# F28335_FanOut.net
KiCad netlist of a schematic drawn in Altium Designer
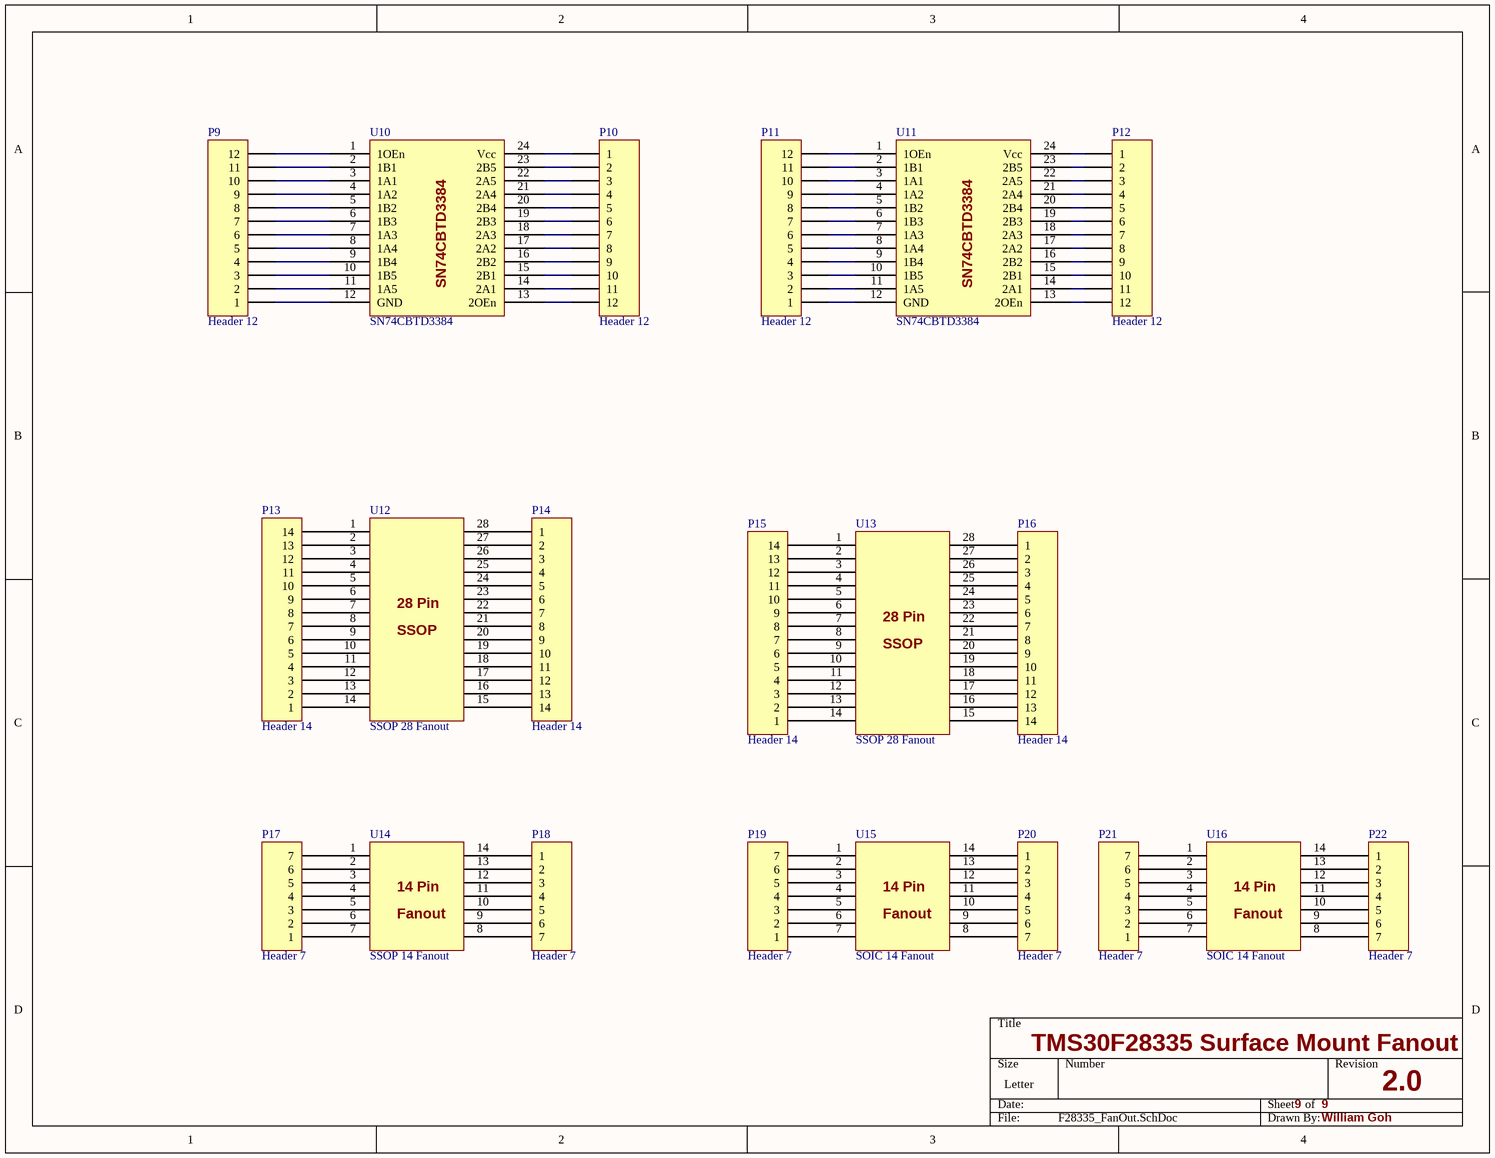
[diagram p0: F28335_FanOut.SchDoc]

(export (version "E")
  (design (tool "Eeschema 10.0.6"))
  (components
    (comp (ref "P9")
      (value "Header 12")
      (footprint "HDR1X12")
      (description "Header, 12-Pin")
      (fields (field (name "PUBLISHER") "Altium Limited"))
      (libsource (lib "Miscellaneous Connectors") (part "Header 12"))
    )
    (comp (ref "P10")
      (value "Header 12")
      (footprint "HDR1X12")
      (description "Header, 12-Pin")
      (fields (field (name "PUBLISHER") "Altium Limited"))
      (libsource (lib "") (part "Header 12_1"))
    )
    (comp (ref "P11")
      (value "Header 12")
      (footprint "HDR1X12")
      (description "Header, 12-Pin")
      (fields (field (name "PUBLISHER") "Altium Limited"))
      (libsource (lib "Miscellaneous Connectors") (part "Header 12"))
    )
    (comp (ref "P12")
      (value "Header 12")
      (footprint "HDR1X12")
      (description "Header, 12-Pin")
      (fields (field (name "PUBLISHER") "Altium Limited"))
      (libsource (lib "") (part "Header 12_1"))
    )
    (comp (ref "P13")
      (value "Header 14")
      (footprint "HDR1X14")
      (description "Header, 14-Pin")
      (fields (field (name "PUBLISHER") "Altium Limited"))
      (libsource (lib "") (part "Header 14_1"))
    )
    (comp (ref "P14")
      (value "Header 14")
      (footprint "HDR1X14")
      (description "Header, 14-Pin")
      (fields (field (name "PUBLISHER") "Altium Limited"))
      (libsource (lib "Miscellaneous Connectors") (part "Header 14"))
    )
    (comp (ref "P15")
      (value "Header 14")
      (footprint "HDR1X14")
      (description "Header, 14-Pin")
      (fields (field (name "PUBLISHER") "Altium Limited"))
      (libsource (lib "") (part "Header 14_1"))
    )
    (comp (ref "P16")
      (value "Header 14")
      (footprint "HDR1X14")
      (description "Header, 14-Pin")
      (fields (field (name "PUBLISHER") "Altium Limited"))
      (libsource (lib "Miscellaneous Connectors") (part "Header 14"))
    )
    (comp (ref "P17")
      (value "Header 7")
      (footprint "HDR1X7")
      (description "Header, 7-Pin")
      (fields (field (name "PUBLISHER") "Altium Limited"))
      (libsource (lib "") (part "Header 7_1"))
    )
    (comp (ref "P18")
      (value "Header 7")
      (footprint "HDR1X7")
      (description "Header, 7-Pin")
      (fields (field (name "PUBLISHER") "Altium Limited"))
      (libsource (lib "Miscellaneous Connectors") (part "Header 7"))
    )
    (comp (ref "P19")
      (value "Header 7")
      (footprint "HDR1X7")
      (description "Header, 7-Pin")
      (fields (field (name "PUBLISHER") "Altium Limited"))
      (libsource (lib "") (part "Header 7_1"))
    )
    (comp (ref "P20")
      (value "Header 7")
      (footprint "HDR1X7")
      (description "Header, 7-Pin")
      (fields (field (name "PUBLISHER") "Altium Limited"))
      (libsource (lib "Miscellaneous Connectors") (part "Header 7"))
    )
    (comp (ref "P21")
      (value "Header 7")
      (footprint "HDR1X7")
      (description "Header, 7-Pin")
      (fields (field (name "PUBLISHER") "Altium Limited"))
      (libsource (lib "") (part "Header 7_1"))
    )
    (comp (ref "P22")
      (value "Header 7")
      (footprint "HDR1X7")
      (description "Header, 7-Pin")
      (fields (field (name "PUBLISHER") "Altium Limited"))
      (libsource (lib "Miscellaneous Connectors") (part "Header 7"))
    )
    (comp (ref "U10")
      (value "SN74CBTD3384")
      (footprint "DW-24")
      (description "10-Bit FET Bus Switches With Level Shifting")
      (libsource (lib "F28335_DSC_Breakout") (part "SN74CBTD3384"))
    )
    (comp (ref "U11")
      (value "SN74CBTD3384")
      (footprint "DW-24")
      (description "10-Bit FET Bus Switches With Level Shifting")
      (libsource (lib "F28335_DSC_Breakout") (part "SN74CBTD3384"))
    )
    (comp (ref "U12")
      (value "SSOP 28 Fanout")
      (footprint "SSOP-28 Fan out")
      (libsource (lib "F28335_DSC_Breakout") (part "SSOP 28 Fanout"))
    )
    (comp (ref "U13")
      (value "SSOP 28 Fanout")
      (footprint "SSOP-28 Fan out")
      (libsource (lib "F28335_DSC_Breakout") (part "SSOP 28 Fanout"))
    )
    (comp (ref "U14")
      (value "SSOP 14 Fanout")
      (footprint "SSOP-14 Fan out")
      (libsource (lib "F28335_DSC_Breakout") (part "SSOP 14 Fanout"))
    )
    (comp (ref "U15")
      (value "SOIC 14 Fanout")
      (footprint "SOIC-14 Fan out")
      (libsource (lib "F28335_DSC_Breakout") (part "SSOP 14 Fanout"))
    )
    (comp (ref "U16")
      (value "SOIC 14 Fanout")
      (footprint "SOIC-14 Fan out")
      (libsource (lib "F28335_DSC_Breakout") (part "SSOP 14 Fanout"))
    )
  )
  (nets
    (net (code "1") (name "Net-(P13-Pad1)") (class "Default")
      (node (ref "P13") (pin "1") (pinfunction "1_1") (pintype "passive"))
      (node (ref "U12") (pin "14") (pintype "passive"))
    )
    (net (code "2") (name "Net-(P13-Pad2)") (class "Default")
      (node (ref "P13") (pin "2") (pinfunction "2_2") (pintype "passive"))
      (node (ref "U12") (pin "13") (pintype "passive"))
    )
    (net (code "3") (name "Net-(P13-Pad3)") (class "Default")
      (node (ref "P13") (pin "3") (pinfunction "3_3") (pintype "passive"))
      (node (ref "U12") (pin "12") (pintype "passive"))
    )
    (net (code "4") (name "Net-(P13-Pad4)") (class "Default")
      (node (ref "P13") (pin "4") (pinfunction "4_4") (pintype "passive"))
      (node (ref "U12") (pin "11") (pintype "passive"))
    )
    (net (code "5") (name "Net-(P13-Pad5)") (class "Default")
      (node (ref "P13") (pin "5") (pinfunction "5_5") (pintype "passive"))
      (node (ref "U12") (pin "10") (pintype "passive"))
    )
    (net (code "6") (name "Net-(P13-Pad6)") (class "Default")
      (node (ref "P13") (pin "6") (pinfunction "6_6") (pintype "passive"))
      (node (ref "U12") (pin "9") (pintype "passive"))
    )
    (net (code "7") (name "Net-(P13-Pad7)") (class "Default")
      (node (ref "P13") (pin "7") (pinfunction "7_7") (pintype "passive"))
      (node (ref "U12") (pin "8") (pintype "passive"))
    )
    (net (code "8") (name "Net-(P13-Pad8)") (class "Default")
      (node (ref "P13") (pin "8") (pinfunction "8_8") (pintype "passive"))
      (node (ref "U12") (pin "7") (pintype "passive"))
    )
    (net (code "9") (name "Net-(P13-Pad9)") (class "Default")
      (node (ref "P13") (pin "9") (pinfunction "9_9") (pintype "passive"))
      (node (ref "U12") (pin "6") (pintype "passive"))
    )
    (net (code "10") (name "Net-(P13-Pad10)") (class "Default")
      (node (ref "P13") (pin "10") (pinfunction "10_10") (pintype "passive"))
      (node (ref "U12") (pin "5") (pintype "passive"))
    )
    (net (code "11") (name "Net-(P13-Pad11)") (class "Default")
      (node (ref "P13") (pin "11") (pinfunction "11_11") (pintype "passive"))
      (node (ref "U12") (pin "4") (pintype "passive"))
    )
    (net (code "12") (name "Net-(P13-Pad12)") (class "Default")
      (node (ref "P13") (pin "12") (pinfunction "12_12") (pintype "passive"))
      (node (ref "U12") (pin "3") (pintype "passive"))
    )
    (net (code "13") (name "Net-(P13-Pad13)") (class "Default")
      (node (ref "P13") (pin "13") (pinfunction "13_13") (pintype "passive"))
      (node (ref "U12") (pin "2") (pintype "passive"))
    )
    (net (code "14") (name "Net-(P13-Pad14)") (class "Default")
      (node (ref "P13") (pin "14") (pinfunction "14_14") (pintype "passive"))
      (node (ref "U12") (pin "1") (pintype "passive"))
    )
    (net (code "15") (name "Net-(P14-Pad1)") (class "Default")
      (node (ref "P14") (pin "1") (pinfunction "1_1") (pintype "passive"))
      (node (ref "U12") (pin "28") (pintype "passive"))
    )
    (net (code "16") (name "Net-(P14-Pad2)") (class "Default")
      (node (ref "P14") (pin "2") (pinfunction "2_2") (pintype "passive"))
      (node (ref "U12") (pin "27") (pintype "passive"))
    )
    (net (code "17") (name "Net-(P14-Pad3)") (class "Default")
      (node (ref "P14") (pin "3") (pinfunction "3_3") (pintype "passive"))
      (node (ref "U12") (pin "26") (pintype "passive"))
    )
    (net (code "18") (name "Net-(P14-Pad4)") (class "Default")
      (node (ref "P14") (pin "4") (pinfunction "4_4") (pintype "passive"))
      (node (ref "U12") (pin "25") (pintype "passive"))
    )
    (net (code "19") (name "Net-(P14-Pad5)") (class "Default")
      (node (ref "P14") (pin "5") (pinfunction "5_5") (pintype "passive"))
      (node (ref "U12") (pin "24") (pintype "passive"))
    )
    (net (code "20") (name "Net-(P14-Pad6)") (class "Default")
      (node (ref "P14") (pin "6") (pinfunction "6_6") (pintype "passive"))
      (node (ref "U12") (pin "23") (pintype "passive"))
    )
    (net (code "21") (name "Net-(P14-Pad7)") (class "Default")
      (node (ref "P14") (pin "7") (pinfunction "7_7") (pintype "passive"))
      (node (ref "U12") (pin "22") (pintype "passive"))
    )
    (net (code "22") (name "Net-(P14-Pad8)") (class "Default")
      (node (ref "P14") (pin "8") (pinfunction "8_8") (pintype "passive"))
      (node (ref "U12") (pin "21") (pintype "passive"))
    )
    (net (code "23") (name "Net-(P14-Pad9)") (class "Default")
      (node (ref "P14") (pin "9") (pinfunction "9_9") (pintype "passive"))
      (node (ref "U12") (pin "20") (pintype "passive"))
    )
    (net (code "24") (name "Net-(P14-Pad10)") (class "Default")
      (node (ref "P14") (pin "10") (pinfunction "10_10") (pintype "passive"))
      (node (ref "U12") (pin "19") (pintype "passive"))
    )
    (net (code "25") (name "Net-(P14-Pad11)") (class "Default")
      (node (ref "P14") (pin "11") (pinfunction "11_11") (pintype "passive"))
      (node (ref "U12") (pin "18") (pintype "passive"))
    )
    (net (code "26") (name "Net-(P14-Pad12)") (class "Default")
      (node (ref "P14") (pin "12") (pinfunction "12_12") (pintype "passive"))
      (node (ref "U12") (pin "17") (pintype "passive"))
    )
    (net (code "27") (name "Net-(P14-Pad13)") (class "Default")
      (node (ref "P14") (pin "13") (pinfunction "13_13") (pintype "passive"))
      (node (ref "U12") (pin "16") (pintype "passive"))
    )
    (net (code "28") (name "Net-(P14-Pad14)") (class "Default")
      (node (ref "P14") (pin "14") (pinfunction "14_14") (pintype "passive"))
      (node (ref "U12") (pin "15") (pintype "passive"))
    )
    (net (code "29") (name "Net-(P15-Pad1)") (class "Default")
      (node (ref "P15") (pin "1") (pinfunction "1_1") (pintype "passive"))
      (node (ref "U13") (pin "14") (pintype "passive"))
    )
    (net (code "30") (name "Net-(P15-Pad2)") (class "Default")
      (node (ref "P15") (pin "2") (pinfunction "2_2") (pintype "passive"))
      (node (ref "U13") (pin "13") (pintype "passive"))
    )
    (net (code "31") (name "Net-(P15-Pad3)") (class "Default")
      (node (ref "P15") (pin "3") (pinfunction "3_3") (pintype "passive"))
      (node (ref "U13") (pin "12") (pintype "passive"))
    )
    (net (code "32") (name "Net-(P15-Pad4)") (class "Default")
      (node (ref "P15") (pin "4") (pinfunction "4_4") (pintype "passive"))
      (node (ref "U13") (pin "11") (pintype "passive"))
    )
    (net (code "33") (name "Net-(P15-Pad5)") (class "Default")
      (node (ref "P15") (pin "5") (pinfunction "5_5") (pintype "passive"))
      (node (ref "U13") (pin "10") (pintype "passive"))
    )
    (net (code "34") (name "Net-(P15-Pad6)") (class "Default")
      (node (ref "P15") (pin "6") (pinfunction "6_6") (pintype "passive"))
      (node (ref "U13") (pin "9") (pintype "passive"))
    )
    (net (code "35") (name "Net-(P15-Pad7)") (class "Default")
      (node (ref "P15") (pin "7") (pinfunction "7_7") (pintype "passive"))
      (node (ref "U13") (pin "8") (pintype "passive"))
    )
    (net (code "36") (name "Net-(P15-Pad8)") (class "Default")
      (node (ref "P15") (pin "8") (pinfunction "8_8") (pintype "passive"))
      (node (ref "U13") (pin "7") (pintype "passive"))
    )
    (net (code "37") (name "Net-(P15-Pad9)") (class "Default")
      (node (ref "P15") (pin "9") (pinfunction "9_9") (pintype "passive"))
      (node (ref "U13") (pin "6") (pintype "passive"))
    )
    (net (code "38") (name "Net-(P15-Pad10)") (class "Default")
      (node (ref "P15") (pin "10") (pinfunction "10_10") (pintype "passive"))
      (node (ref "U13") (pin "5") (pintype "passive"))
    )
    (net (code "39") (name "Net-(P15-Pad11)") (class "Default")
      (node (ref "P15") (pin "11") (pinfunction "11_11") (pintype "passive"))
      (node (ref "U13") (pin "4") (pintype "passive"))
    )
    (net (code "40") (name "Net-(P15-Pad12)") (class "Default")
      (node (ref "P15") (pin "12") (pinfunction "12_12") (pintype "passive"))
      (node (ref "U13") (pin "3") (pintype "passive"))
    )
    (net (code "41") (name "Net-(P15-Pad13)") (class "Default")
      (node (ref "P15") (pin "13") (pinfunction "13_13") (pintype "passive"))
      (node (ref "U13") (pin "2") (pintype "passive"))
    )
    (net (code "42") (name "Net-(P15-Pad14)") (class "Default")
      (node (ref "P15") (pin "14") (pinfunction "14_14") (pintype "passive"))
      (node (ref "U13") (pin "1") (pintype "passive"))
    )
    (net (code "43") (name "Net-(P16-Pad1)") (class "Default")
      (node (ref "P16") (pin "1") (pinfunction "1_1") (pintype "passive"))
      (node (ref "U13") (pin "28") (pintype "passive"))
    )
    (net (code "44") (name "Net-(P16-Pad2)") (class "Default")
      (node (ref "P16") (pin "2") (pinfunction "2_2") (pintype "passive"))
      (node (ref "U13") (pin "27") (pintype "passive"))
    )
    (net (code "45") (name "Net-(P16-Pad3)") (class "Default")
      (node (ref "P16") (pin "3") (pinfunction "3_3") (pintype "passive"))
      (node (ref "U13") (pin "26") (pintype "passive"))
    )
    (net (code "46") (name "Net-(P16-Pad4)") (class "Default")
      (node (ref "P16") (pin "4") (pinfunction "4_4") (pintype "passive"))
      (node (ref "U13") (pin "25") (pintype "passive"))
    )
    (net (code "47") (name "Net-(P16-Pad5)") (class "Default")
      (node (ref "P16") (pin "5") (pinfunction "5_5") (pintype "passive"))
      (node (ref "U13") (pin "24") (pintype "passive"))
    )
    (net (code "48") (name "Net-(P16-Pad6)") (class "Default")
      (node (ref "P16") (pin "6") (pinfunction "6_6") (pintype "passive"))
      (node (ref "U13") (pin "23") (pintype "passive"))
    )
    (net (code "49") (name "Net-(P16-Pad7)") (class "Default")
      (node (ref "P16") (pin "7") (pinfunction "7_7") (pintype "passive"))
      (node (ref "U13") (pin "22") (pintype "passive"))
    )
    (net (code "50") (name "Net-(P16-Pad8)") (class "Default")
      (node (ref "P16") (pin "8") (pinfunction "8_8") (pintype "passive"))
      (node (ref "U13") (pin "21") (pintype "passive"))
    )
    (net (code "51") (name "Net-(P16-Pad9)") (class "Default")
      (node (ref "P16") (pin "9") (pinfunction "9_9") (pintype "passive"))
      (node (ref "U13") (pin "20") (pintype "passive"))
    )
    (net (code "52") (name "Net-(P16-Pad10)") (class "Default")
      (node (ref "P16") (pin "10") (pinfunction "10_10") (pintype "passive"))
      (node (ref "U13") (pin "19") (pintype "passive"))
    )
    (net (code "53") (name "Net-(P16-Pad11)") (class "Default")
      (node (ref "P16") (pin "11") (pinfunction "11_11") (pintype "passive"))
      (node (ref "U13") (pin "18") (pintype "passive"))
    )
    (net (code "54") (name "Net-(P16-Pad12)") (class "Default")
      (node (ref "P16") (pin "12") (pinfunction "12_12") (pintype "passive"))
      (node (ref "U13") (pin "17") (pintype "passive"))
    )
    (net (code "55") (name "Net-(P16-Pad13)") (class "Default")
      (node (ref "P16") (pin "13") (pinfunction "13_13") (pintype "passive"))
      (node (ref "U13") (pin "16") (pintype "passive"))
    )
    (net (code "56") (name "Net-(P16-Pad14)") (class "Default")
      (node (ref "P16") (pin "14") (pinfunction "14_14") (pintype "passive"))
      (node (ref "U13") (pin "15") (pintype "passive"))
    )
    (net (code "57") (name "Net-(P17-Pad1)") (class "Default")
      (node (ref "P17") (pin "1") (pinfunction "1_1") (pintype "passive"))
      (node (ref "U14") (pin "7") (pintype "passive"))
    )
    (net (code "58") (name "Net-(P17-Pad2)") (class "Default")
      (node (ref "P17") (pin "2") (pinfunction "2_2") (pintype "passive"))
      (node (ref "U14") (pin "6") (pintype "passive"))
    )
    (net (code "59") (name "Net-(P17-Pad3)") (class "Default")
      (node (ref "P17") (pin "3") (pinfunction "3_3") (pintype "passive"))
      (node (ref "U14") (pin "5") (pintype "passive"))
    )
    (net (code "60") (name "Net-(P17-Pad4)") (class "Default")
      (node (ref "P17") (pin "4") (pinfunction "4_4") (pintype "passive"))
      (node (ref "U14") (pin "4") (pintype "passive"))
    )
    (net (code "61") (name "Net-(P17-Pad5)") (class "Default")
      (node (ref "P17") (pin "5") (pinfunction "5_5") (pintype "passive"))
      (node (ref "U14") (pin "3") (pintype "passive"))
    )
    (net (code "62") (name "Net-(P17-Pad6)") (class "Default")
      (node (ref "P17") (pin "6") (pinfunction "6_6") (pintype "passive"))
      (node (ref "U14") (pin "2") (pintype "passive"))
    )
    (net (code "63") (name "Net-(P17-Pad7)") (class "Default")
      (node (ref "P17") (pin "7") (pinfunction "7_7") (pintype "passive"))
      (node (ref "U14") (pin "1") (pintype "passive"))
    )
    (net (code "64") (name "Net-(P18-Pad1)") (class "Default")
      (node (ref "P18") (pin "1") (pinfunction "1_1") (pintype "passive"))
      (node (ref "U14") (pin "14") (pintype "passive"))
    )
    (net (code "65") (name "Net-(P18-Pad2)") (class "Default")
      (node (ref "P18") (pin "2") (pinfunction "2_2") (pintype "passive"))
      (node (ref "U14") (pin "13") (pintype "passive"))
    )
    (net (code "66") (name "Net-(P18-Pad3)") (class "Default")
      (node (ref "P18") (pin "3") (pinfunction "3_3") (pintype "passive"))
      (node (ref "U14") (pin "12") (pintype "passive"))
    )
    (net (code "67") (name "Net-(P18-Pad4)") (class "Default")
      (node (ref "P18") (pin "4") (pinfunction "4_4") (pintype "passive"))
      (node (ref "U14") (pin "11") (pintype "passive"))
    )
    (net (code "68") (name "Net-(P18-Pad5)") (class "Default")
      (node (ref "P18") (pin "5") (pinfunction "5_5") (pintype "passive"))
      (node (ref "U14") (pin "10") (pintype "passive"))
    )
    (net (code "69") (name "Net-(P18-Pad6)") (class "Default")
      (node (ref "P18") (pin "6") (pinfunction "6_6") (pintype "passive"))
      (node (ref "U14") (pin "9") (pintype "passive"))
    )
    (net (code "70") (name "Net-(P18-Pad7)") (class "Default")
      (node (ref "P18") (pin "7") (pinfunction "7_7") (pintype "passive"))
      (node (ref "U14") (pin "8") (pintype "passive"))
    )
    (net (code "71") (name "Net-(P19-Pad1)") (class "Default")
      (node (ref "P19") (pin "1") (pinfunction "1_1") (pintype "passive"))
      (node (ref "U15") (pin "7") (pintype "passive"))
    )
    (net (code "72") (name "Net-(P19-Pad2)") (class "Default")
      (node (ref "P19") (pin "2") (pinfunction "2_2") (pintype "passive"))
      (node (ref "U15") (pin "6") (pintype "passive"))
    )
    (net (code "73") (name "Net-(P19-Pad3)") (class "Default")
      (node (ref "P19") (pin "3") (pinfunction "3_3") (pintype "passive"))
      (node (ref "U15") (pin "5") (pintype "passive"))
    )
    (net (code "74") (name "Net-(P19-Pad4)") (class "Default")
      (node (ref "P19") (pin "4") (pinfunction "4_4") (pintype "passive"))
      (node (ref "U15") (pin "4") (pintype "passive"))
    )
    (net (code "75") (name "Net-(P19-Pad5)") (class "Default")
      (node (ref "P19") (pin "5") (pinfunction "5_5") (pintype "passive"))
      (node (ref "U15") (pin "3") (pintype "passive"))
    )
    (net (code "76") (name "Net-(P19-Pad6)") (class "Default")
      (node (ref "P19") (pin "6") (pinfunction "6_6") (pintype "passive"))
      (node (ref "U15") (pin "2") (pintype "passive"))
    )
    (net (code "77") (name "Net-(P19-Pad7)") (class "Default")
      (node (ref "P19") (pin "7") (pinfunction "7_7") (pintype "passive"))
      (node (ref "U15") (pin "1") (pintype "passive"))
    )
    (net (code "78") (name "Net-(P20-Pad1)") (class "Default")
      (node (ref "P20") (pin "1") (pinfunction "1_1") (pintype "passive"))
      (node (ref "U15") (pin "14") (pintype "passive"))
    )
    (net (code "79") (name "Net-(P20-Pad2)") (class "Default")
      (node (ref "P20") (pin "2") (pinfunction "2_2") (pintype "passive"))
      (node (ref "U15") (pin "13") (pintype "passive"))
    )
    (net (code "80") (name "Net-(P20-Pad3)") (class "Default")
      (node (ref "P20") (pin "3") (pinfunction "3_3") (pintype "passive"))
      (node (ref "U15") (pin "12") (pintype "passive"))
    )
    (net (code "81") (name "Net-(P20-Pad4)") (class "Default")
      (node (ref "P20") (pin "4") (pinfunction "4_4") (pintype "passive"))
      (node (ref "U15") (pin "11") (pintype "passive"))
    )
    (net (code "82") (name "Net-(P20-Pad5)") (class "Default")
      (node (ref "P20") (pin "5") (pinfunction "5_5") (pintype "passive"))
      (node (ref "U15") (pin "10") (pintype "passive"))
    )
    (net (code "83") (name "Net-(P20-Pad6)") (class "Default")
      (node (ref "P20") (pin "6") (pinfunction "6_6") (pintype "passive"))
      (node (ref "U15") (pin "9") (pintype "passive"))
    )
    (net (code "84") (name "Net-(P20-Pad7)") (class "Default")
      (node (ref "P20") (pin "7") (pinfunction "7_7") (pintype "passive"))
      (node (ref "U15") (pin "8") (pintype "passive"))
    )
    (net (code "85") (name "Net-(P21-Pad1)") (class "Default")
      (node (ref "P21") (pin "1") (pinfunction "1_1") (pintype "passive"))
      (node (ref "U16") (pin "7") (pintype "passive"))
    )
    (net (code "86") (name "Net-(P21-Pad2)") (class "Default")
      (node (ref "P21") (pin "2") (pinfunction "2_2") (pintype "passive"))
      (node (ref "U16") (pin "6") (pintype "passive"))
    )
    (net (code "87") (name "Net-(P21-Pad3)") (class "Default")
      (node (ref "P21") (pin "3") (pinfunction "3_3") (pintype "passive"))
      (node (ref "U16") (pin "5") (pintype "passive"))
    )
    (net (code "88") (name "Net-(P21-Pad4)") (class "Default")
      (node (ref "P21") (pin "4") (pinfunction "4_4") (pintype "passive"))
      (node (ref "U16") (pin "4") (pintype "passive"))
    )
    (net (code "89") (name "Net-(P21-Pad5)") (class "Default")
      (node (ref "P21") (pin "5") (pinfunction "5_5") (pintype "passive"))
      (node (ref "U16") (pin "3") (pintype "passive"))
    )
    (net (code "90") (name "Net-(P21-Pad6)") (class "Default")
      (node (ref "P21") (pin "6") (pinfunction "6_6") (pintype "passive"))
      (node (ref "U16") (pin "2") (pintype "passive"))
    )
    (net (code "91") (name "Net-(P21-Pad7)") (class "Default")
      (node (ref "P21") (pin "7") (pinfunction "7_7") (pintype "passive"))
      (node (ref "U16") (pin "1") (pintype "passive"))
    )
    (net (code "92") (name "Net-(P22-Pad1)") (class "Default")
      (node (ref "P22") (pin "1") (pinfunction "1_1") (pintype "passive"))
      (node (ref "U16") (pin "14") (pintype "passive"))
    )
    (net (code "93") (name "Net-(P22-Pad2)") (class "Default")
      (node (ref "P22") (pin "2") (pinfunction "2_2") (pintype "passive"))
      (node (ref "U16") (pin "13") (pintype "passive"))
    )
    (net (code "94") (name "Net-(P22-Pad3)") (class "Default")
      (node (ref "P22") (pin "3") (pinfunction "3_3") (pintype "passive"))
      (node (ref "U16") (pin "12") (pintype "passive"))
    )
    (net (code "95") (name "Net-(P22-Pad4)") (class "Default")
      (node (ref "P22") (pin "4") (pinfunction "4_4") (pintype "passive"))
      (node (ref "U16") (pin "11") (pintype "passive"))
    )
    (net (code "96") (name "Net-(P22-Pad5)") (class "Default")
      (node (ref "P22") (pin "5") (pinfunction "5_5") (pintype "passive"))
      (node (ref "U16") (pin "10") (pintype "passive"))
    )
    (net (code "97") (name "Net-(P22-Pad6)") (class "Default")
      (node (ref "P22") (pin "6") (pinfunction "6_6") (pintype "passive"))
      (node (ref "U16") (pin "9") (pintype "passive"))
    )
    (net (code "98") (name "Net-(P22-Pad7)") (class "Default")
      (node (ref "P22") (pin "7") (pinfunction "7_7") (pintype "passive"))
      (node (ref "U16") (pin "8") (pintype "passive"))
    )
    (net (code "99") (name "Net-(U10-1A1)") (class "Default")
      (node (ref "P9") (pin "10") (pinfunction "10_10") (pintype "passive"))
      (node (ref "U10") (pin "3") (pinfunction "1A1_3") (pintype "passive"))
    )
    (net (code "100") (name "Net-(U10-1A2)") (class "Default")
      (node (ref "P9") (pin "9") (pinfunction "9_9") (pintype "passive"))
      (node (ref "U10") (pin "4") (pinfunction "1A2_4") (pintype "passive"))
    )
    (net (code "101") (name "Net-(U10-1A3)") (class "Default")
      (node (ref "P9") (pin "6") (pinfunction "6_6") (pintype "passive"))
      (node (ref "U10") (pin "7") (pinfunction "1A3_7") (pintype "passive"))
    )
    (net (code "102") (name "Net-(U10-1A4)") (class "Default")
      (node (ref "P9") (pin "5") (pinfunction "5_5") (pintype "passive"))
      (node (ref "U10") (pin "8") (pinfunction "1A4_8") (pintype "passive"))
    )
    (net (code "103") (name "Net-(U10-1A5)") (class "Default")
      (node (ref "P9") (pin "2") (pinfunction "2_2") (pintype "passive"))
      (node (ref "U10") (pin "11") (pinfunction "1A5_11") (pintype "passive"))
    )
    (net (code "104") (name "Net-(U10-1B1)") (class "Default")
      (node (ref "P9") (pin "11") (pinfunction "11_11") (pintype "passive"))
      (node (ref "U10") (pin "2") (pinfunction "1B1_2") (pintype "passive"))
    )
    (net (code "105") (name "Net-(U10-1B2)") (class "Default")
      (node (ref "P9") (pin "8") (pinfunction "8_8") (pintype "passive"))
      (node (ref "U10") (pin "5") (pinfunction "1B2_5") (pintype "passive"))
    )
    (net (code "106") (name "Net-(U10-1B3)") (class "Default")
      (node (ref "P9") (pin "7") (pinfunction "7_7") (pintype "passive"))
      (node (ref "U10") (pin "6") (pinfunction "1B3_6") (pintype "passive"))
    )
    (net (code "107") (name "Net-(U10-1B4)") (class "Default")
      (node (ref "P9") (pin "4") (pinfunction "4_4") (pintype "passive"))
      (node (ref "U10") (pin "9") (pinfunction "1B4_9") (pintype "passive"))
    )
    (net (code "108") (name "Net-(U10-1B5)") (class "Default")
      (node (ref "P9") (pin "3") (pinfunction "3_3") (pintype "passive"))
      (node (ref "U10") (pin "10") (pinfunction "1B5_10") (pintype "passive"))
    )
    (net (code "109") (name "Net-(U10-1OEn)") (class "Default")
      (node (ref "P9") (pin "12") (pinfunction "12_12") (pintype "passive"))
      (node (ref "U10") (pin "1") (pinfunction "1OEn_1") (pintype "passive"))
    )
    (net (code "110") (name "Net-(U10-2A1)") (class "Default")
      (node (ref "P10") (pin "11") (pinfunction "11_11") (pintype "passive"))
      (node (ref "U10") (pin "14") (pinfunction "2A1_14") (pintype "passive"))
    )
    (net (code "111") (name "Net-(U10-2A2)") (class "Default")
      (node (ref "P10") (pin "8") (pinfunction "8_8") (pintype "passive"))
      (node (ref "U10") (pin "17") (pinfunction "2A2_17") (pintype "passive"))
    )
    (net (code "112") (name "Net-(U10-2A3)") (class "Default")
      (node (ref "P10") (pin "7") (pinfunction "7_7") (pintype "passive"))
      (node (ref "U10") (pin "18") (pinfunction "2A3_18") (pintype "passive"))
    )
    (net (code "113") (name "Net-(U10-2A4)") (class "Default")
      (node (ref "P10") (pin "4") (pinfunction "4_4") (pintype "passive"))
      (node (ref "U10") (pin "21") (pinfunction "2A4_21") (pintype "passive"))
    )
    (net (code "114") (name "Net-(U10-2A5)") (class "Default")
      (node (ref "P10") (pin "3") (pinfunction "3_3") (pintype "passive"))
      (node (ref "U10") (pin "22") (pinfunction "2A5_22") (pintype "passive"))
    )
    (net (code "115") (name "Net-(U10-2B1)") (class "Default")
      (node (ref "P10") (pin "10") (pinfunction "10_10") (pintype "passive"))
      (node (ref "U10") (pin "15") (pinfunction "2B1_15") (pintype "passive"))
    )
    (net (code "116") (name "Net-(U10-2B2)") (class "Default")
      (node (ref "P10") (pin "9") (pinfunction "9_9") (pintype "passive"))
      (node (ref "U10") (pin "16") (pinfunction "2B2_16") (pintype "passive"))
    )
    (net (code "117") (name "Net-(U10-2B3)") (class "Default")
      (node (ref "P10") (pin "6") (pinfunction "6_6") (pintype "passive"))
      (node (ref "U10") (pin "19") (pinfunction "2B3_19") (pintype "passive"))
    )
    (net (code "118") (name "Net-(U10-2B4)") (class "Default")
      (node (ref "P10") (pin "5") (pinfunction "5_5") (pintype "passive"))
      (node (ref "U10") (pin "20") (pinfunction "2B4_20") (pintype "passive"))
    )
    (net (code "119") (name "Net-(U10-2B5)") (class "Default")
      (node (ref "P10") (pin "2") (pinfunction "2_2") (pintype "passive"))
      (node (ref "U10") (pin "23") (pinfunction "2B5_23") (pintype "passive"))
    )
    (net (code "120") (name "Net-(U10-2OEn)") (class "Default")
      (node (ref "P10") (pin "12") (pinfunction "12_12") (pintype "passive"))
      (node (ref "U10") (pin "13") (pinfunction "2OEn_13") (pintype "passive"))
    )
    (net (code "121") (name "Net-(U10-GND)") (class "Default")
      (node (ref "P9") (pin "1") (pinfunction "1_1") (pintype "passive"))
      (node (ref "U10") (pin "12") (pinfunction "GND_12") (pintype "passive"))
    )
    (net (code "122") (name "Net-(U10-Vcc)") (class "Default")
      (node (ref "P10") (pin "1") (pinfunction "1_1") (pintype "passive"))
      (node (ref "U10") (pin "24") (pinfunction "Vcc_24") (pintype "passive"))
    )
    (net (code "123") (name "Net-(U11-1A1)") (class "Default")
      (node (ref "P11") (pin "10") (pinfunction "10_10") (pintype "passive"))
      (node (ref "U11") (pin "3") (pinfunction "1A1_3") (pintype "passive"))
    )
    (net (code "124") (name "Net-(U11-1A2)") (class "Default")
      (node (ref "P11") (pin "9") (pinfunction "9_9") (pintype "passive"))
      (node (ref "U11") (pin "4") (pinfunction "1A2_4") (pintype "passive"))
    )
    (net (code "125") (name "Net-(U11-1A3)") (class "Default")
      (node (ref "P11") (pin "6") (pinfunction "6_6") (pintype "passive"))
      (node (ref "U11") (pin "7") (pinfunction "1A3_7") (pintype "passive"))
    )
    (net (code "126") (name "Net-(U11-1A4)") (class "Default")
      (node (ref "P11") (pin "5") (pinfunction "5_5") (pintype "passive"))
      (node (ref "U11") (pin "8") (pinfunction "1A4_8") (pintype "passive"))
    )
    (net (code "127") (name "Net-(U11-1A5)") (class "Default")
      (node (ref "P11") (pin "2") (pinfunction "2_2") (pintype "passive"))
      (node (ref "U11") (pin "11") (pinfunction "1A5_11") (pintype "passive"))
    )
    (net (code "128") (name "Net-(U11-1B1)") (class "Default")
      (node (ref "P11") (pin "11") (pinfunction "11_11") (pintype "passive"))
      (node (ref "U11") (pin "2") (pinfunction "1B1_2") (pintype "passive"))
    )
    (net (code "129") (name "Net-(U11-1B2)") (class "Default")
      (node (ref "P11") (pin "8") (pinfunction "8_8") (pintype "passive"))
      (node (ref "U11") (pin "5") (pinfunction "1B2_5") (pintype "passive"))
    )
    (net (code "130") (name "Net-(U11-1B3)") (class "Default")
      (node (ref "P11") (pin "7") (pinfunction "7_7") (pintype "passive"))
      (node (ref "U11") (pin "6") (pinfunction "1B3_6") (pintype "passive"))
    )
    (net (code "131") (name "Net-(U11-1B4)") (class "Default")
      (node (ref "P11") (pin "4") (pinfunction "4_4") (pintype "passive"))
      (node (ref "U11") (pin "9") (pinfunction "1B4_9") (pintype "passive"))
    )
    (net (code "132") (name "Net-(U11-1B5)") (class "Default")
      (node (ref "P11") (pin "3") (pinfunction "3_3") (pintype "passive"))
      (node (ref "U11") (pin "10") (pinfunction "1B5_10") (pintype "passive"))
    )
    (net (code "133") (name "Net-(U11-1OEn)") (class "Default")
      (node (ref "P11") (pin "12") (pinfunction "12_12") (pintype "passive"))
      (node (ref "U11") (pin "1") (pinfunction "1OEn_1") (pintype "passive"))
    )
    (net (code "134") (name "Net-(U11-2A1)") (class "Default")
      (node (ref "P12") (pin "11") (pinfunction "11_11") (pintype "passive"))
      (node (ref "U11") (pin "14") (pinfunction "2A1_14") (pintype "passive"))
    )
    (net (code "135") (name "Net-(U11-2A2)") (class "Default")
      (node (ref "P12") (pin "8") (pinfunction "8_8") (pintype "passive"))
      (node (ref "U11") (pin "17") (pinfunction "2A2_17") (pintype "passive"))
    )
    (net (code "136") (name "Net-(U11-2A3)") (class "Default")
      (node (ref "P12") (pin "7") (pinfunction "7_7") (pintype "passive"))
      (node (ref "U11") (pin "18") (pinfunction "2A3_18") (pintype "passive"))
    )
    (net (code "137") (name "Net-(U11-2A4)") (class "Default")
      (node (ref "P12") (pin "4") (pinfunction "4_4") (pintype "passive"))
      (node (ref "U11") (pin "21") (pinfunction "2A4_21") (pintype "passive"))
    )
    (net (code "138") (name "Net-(U11-2A5)") (class "Default")
      (node (ref "P12") (pin "3") (pinfunction "3_3") (pintype "passive"))
      (node (ref "U11") (pin "22") (pinfunction "2A5_22") (pintype "passive"))
    )
    (net (code "139") (name "Net-(U11-2B1)") (class "Default")
      (node (ref "P12") (pin "10") (pinfunction "10_10") (pintype "passive"))
      (node (ref "U11") (pin "15") (pinfunction "2B1_15") (pintype "passive"))
    )
    (net (code "140") (name "Net-(U11-2B2)") (class "Default")
      (node (ref "P12") (pin "9") (pinfunction "9_9") (pintype "passive"))
      (node (ref "U11") (pin "16") (pinfunction "2B2_16") (pintype "passive"))
    )
    (net (code "141") (name "Net-(U11-2B3)") (class "Default")
      (node (ref "P12") (pin "6") (pinfunction "6_6") (pintype "passive"))
      (node (ref "U11") (pin "19") (pinfunction "2B3_19") (pintype "passive"))
    )
    (net (code "142") (name "Net-(U11-2B4)") (class "Default")
      (node (ref "P12") (pin "5") (pinfunction "5_5") (pintype "passive"))
      (node (ref "U11") (pin "20") (pinfunction "2B4_20") (pintype "passive"))
    )
    (net (code "143") (name "Net-(U11-2B5)") (class "Default")
      (node (ref "P12") (pin "2") (pinfunction "2_2") (pintype "passive"))
      (node (ref "U11") (pin "23") (pinfunction "2B5_23") (pintype "passive"))
    )
    (net (code "144") (name "Net-(U11-2OEn)") (class "Default")
      (node (ref "P12") (pin "12") (pinfunction "12_12") (pintype "passive"))
      (node (ref "U11") (pin "13") (pinfunction "2OEn_13") (pintype "passive"))
    )
    (net (code "145") (name "Net-(U11-GND)") (class "Default")
      (node (ref "P11") (pin "1") (pinfunction "1_1") (pintype "passive"))
      (node (ref "U11") (pin "12") (pinfunction "GND_12") (pintype "passive"))
    )
    (net (code "146") (name "Net-(U11-Vcc)") (class "Default")
      (node (ref "P12") (pin "1") (pinfunction "1_1") (pintype "passive"))
      (node (ref "U11") (pin "24") (pinfunction "Vcc_24") (pintype "passive"))
    )
  )
)
